# DM35_Power_C_V1_0.net
KiCad netlist of a schematic drawn in Altium Designer
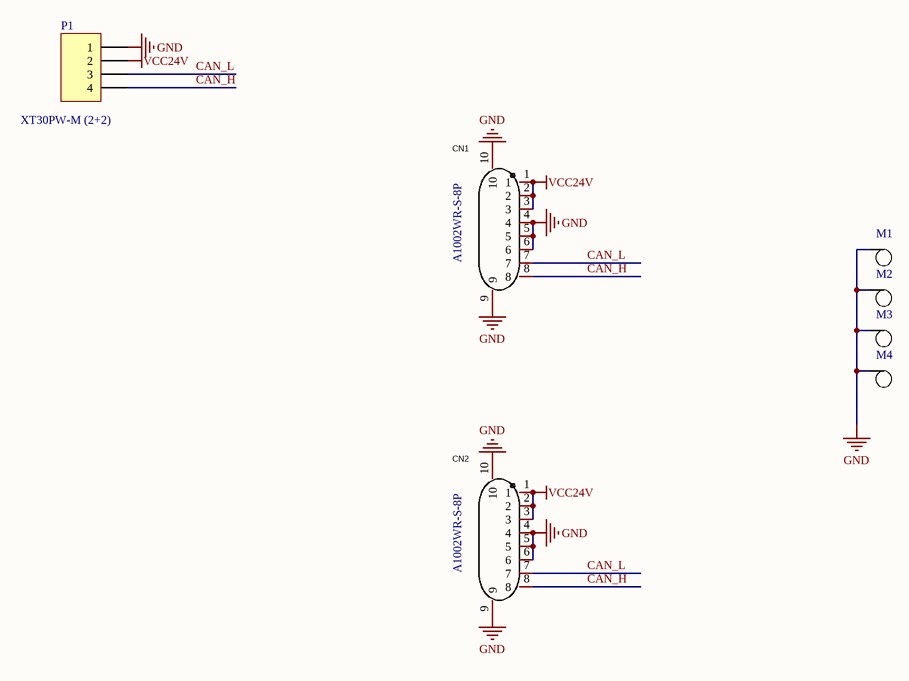
[diagram p0: DM35_Power_C_V1.0.SchDoc]

(export (version "E")
  (design (tool "Eeschema 10.0.6"))
  (components
    (comp (ref "CN1")
      (value "A1002WR-S-8P")
      (footprint "CONN-SMD_A1002WR-S-8P")
      (fields (field (name "MANUFACTURER") "CJT(长江连接器)"))
      (libsource (lib "dm-sch_library") (part "A1002WR-S-8P"))
    )
    (comp (ref "CN2")
      (value "A1002WR-S-8P")
      (footprint "CONN-SMD_A1002WR-S-8P")
      (fields (field (name "MANUFACTURER") "CJT(长江连接器)"))
      (libsource (lib "dm-sch_library") (part "A1002WR-S-8P"))
    )
    (comp (ref "M1")
      (value "M2")
      (footprint "HOLE_PC4DC2P4")
      (libsource (lib "ROBO_V01_2015-DESKTOP-643COGG") (part "Hole-M2.5"))
    )
    (comp (ref "M2")
      (value "M2")
      (footprint "HOLE_PC4DC2P4")
      (libsource (lib "ROBO_V01_2015-DESKTOP-643COGG") (part "Hole-M2.5"))
    )
    (comp (ref "M3")
      (value "M2")
      (footprint "HOLE_PC4DC2P4")
      (libsource (lib "ROBO_V01_2015-DESKTOP-643COGG") (part "Hole-M2.5"))
    )
    (comp (ref "M4")
      (value "M2")
      (footprint "HOLE_PC4DC2P4")
      (libsource (lib "ROBO_V01_2015-DESKTOP-643COGG") (part "Hole-M2.5"))
    )
    (comp (ref "P1")
      (value "XT30PW-M (2+2)")
      (footprint "XT30PW-M (2+2)")
      (fields (field (name "PUBLISHER") "Altium Limited"))
      (libsource (lib "Miscellaneous Connectors") (part "Header 4"))
    )
  )
  (nets
    (net (code "1") (name "/CAN_H") (class "Default")
      (node (ref "CN1") (pin "8") (pinfunction "8_8") (pintype "passive"))
      (node (ref "CN2") (pin "8") (pinfunction "8_8") (pintype "passive"))
      (node (ref "P1") (pin "4") (pinfunction "4_4") (pintype "passive"))
    )
    (net (code "2") (name "/CAN_L") (class "Default")
      (node (ref "CN1") (pin "7") (pinfunction "7_7") (pintype "passive"))
      (node (ref "CN2") (pin "7") (pinfunction "7_7") (pintype "passive"))
      (node (ref "P1") (pin "3") (pinfunction "3_3") (pintype "passive"))
    )
    (net (code "3") (name "GND") (class "Default")
      (node (ref "CN1") (pin "10") (pinfunction "10_10") (pintype "passive"))
      (node (ref "CN1") (pin "4") (pinfunction "4_4") (pintype "passive"))
      (node (ref "CN1") (pin "5") (pinfunction "5_5") (pintype "passive"))
      (node (ref "CN1") (pin "6") (pinfunction "6_6") (pintype "passive"))
      (node (ref "CN1") (pin "9") (pinfunction "9_9") (pintype "passive"))
      (node (ref "CN2") (pin "10") (pinfunction "10_10") (pintype "passive"))
      (node (ref "CN2") (pin "4") (pinfunction "4_4") (pintype "passive"))
      (node (ref "CN2") (pin "5") (pinfunction "5_5") (pintype "passive"))
      (node (ref "CN2") (pin "6") (pinfunction "6_6") (pintype "passive"))
      (node (ref "CN2") (pin "9") (pinfunction "9_9") (pintype "passive"))
      (node (ref "M1") (pin "0") (pinfunction "0_0") (pintype "passive"))
      (node (ref "M2") (pin "0") (pinfunction "0_0") (pintype "passive"))
      (node (ref "M3") (pin "0") (pinfunction "0_0") (pintype "passive"))
      (node (ref "M4") (pin "0") (pinfunction "0_0") (pintype "passive"))
      (node (ref "P1") (pin "1") (pinfunction "1_1") (pintype "passive"))
    )
    (net (code "4") (name "VCC24V") (class "Default")
      (node (ref "CN1") (pin "1") (pinfunction "1_1") (pintype "passive"))
      (node (ref "CN1") (pin "2") (pinfunction "2_2") (pintype "passive"))
      (node (ref "CN1") (pin "3") (pinfunction "3_3") (pintype "passive"))
      (node (ref "CN2") (pin "1") (pinfunction "1_1") (pintype "passive"))
      (node (ref "CN2") (pin "2") (pinfunction "2_2") (pintype "passive"))
      (node (ref "CN2") (pin "3") (pinfunction "3_3") (pintype "passive"))
      (node (ref "P1") (pin "2") (pinfunction "2_2") (pintype "passive"))
    )
  )
)
